# freeDSP.net
KiCad netlist of a schematic drawn in EAGLE
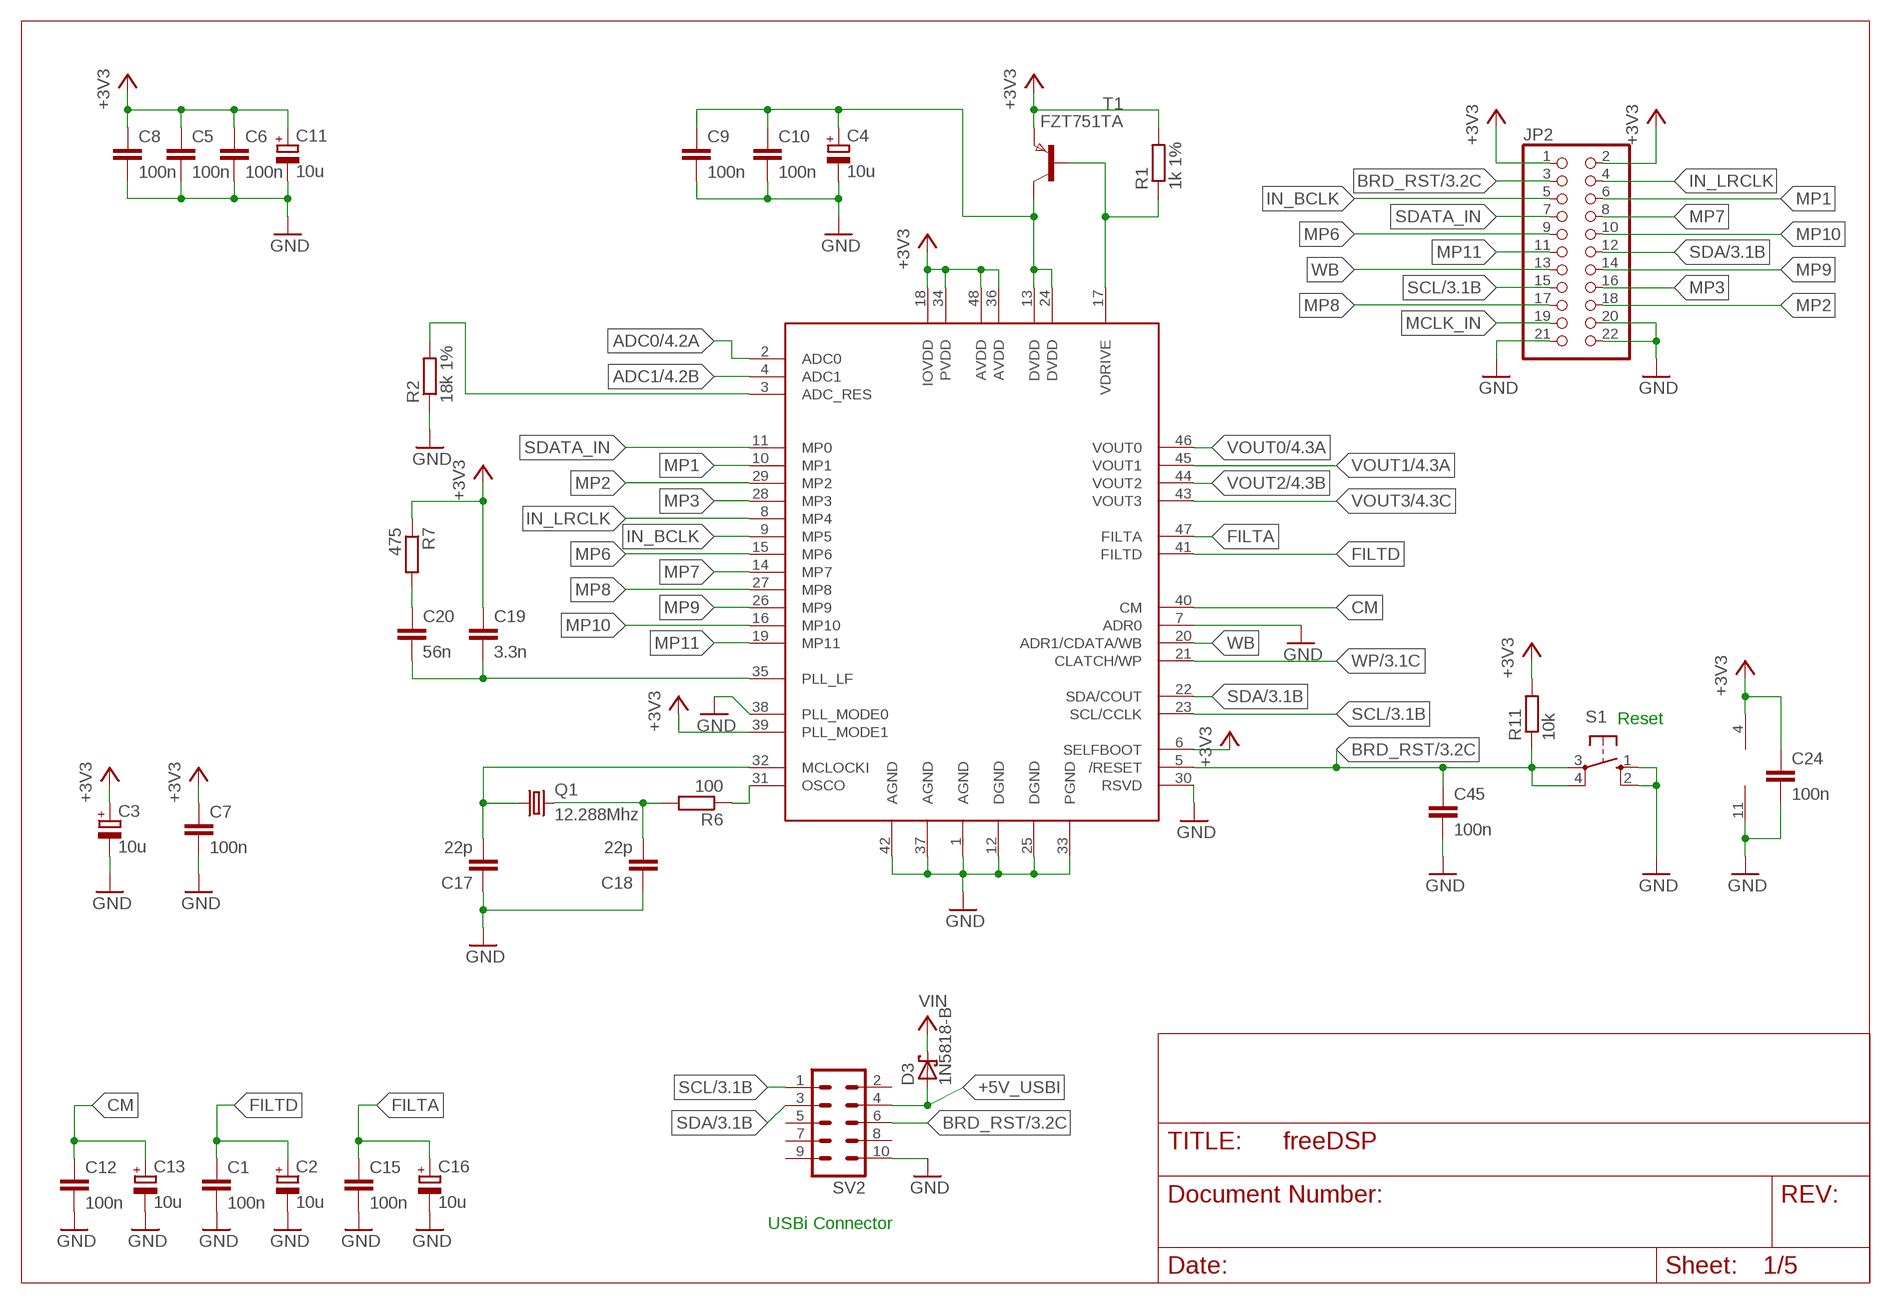
[diagram p0: schematic, sheet 1]
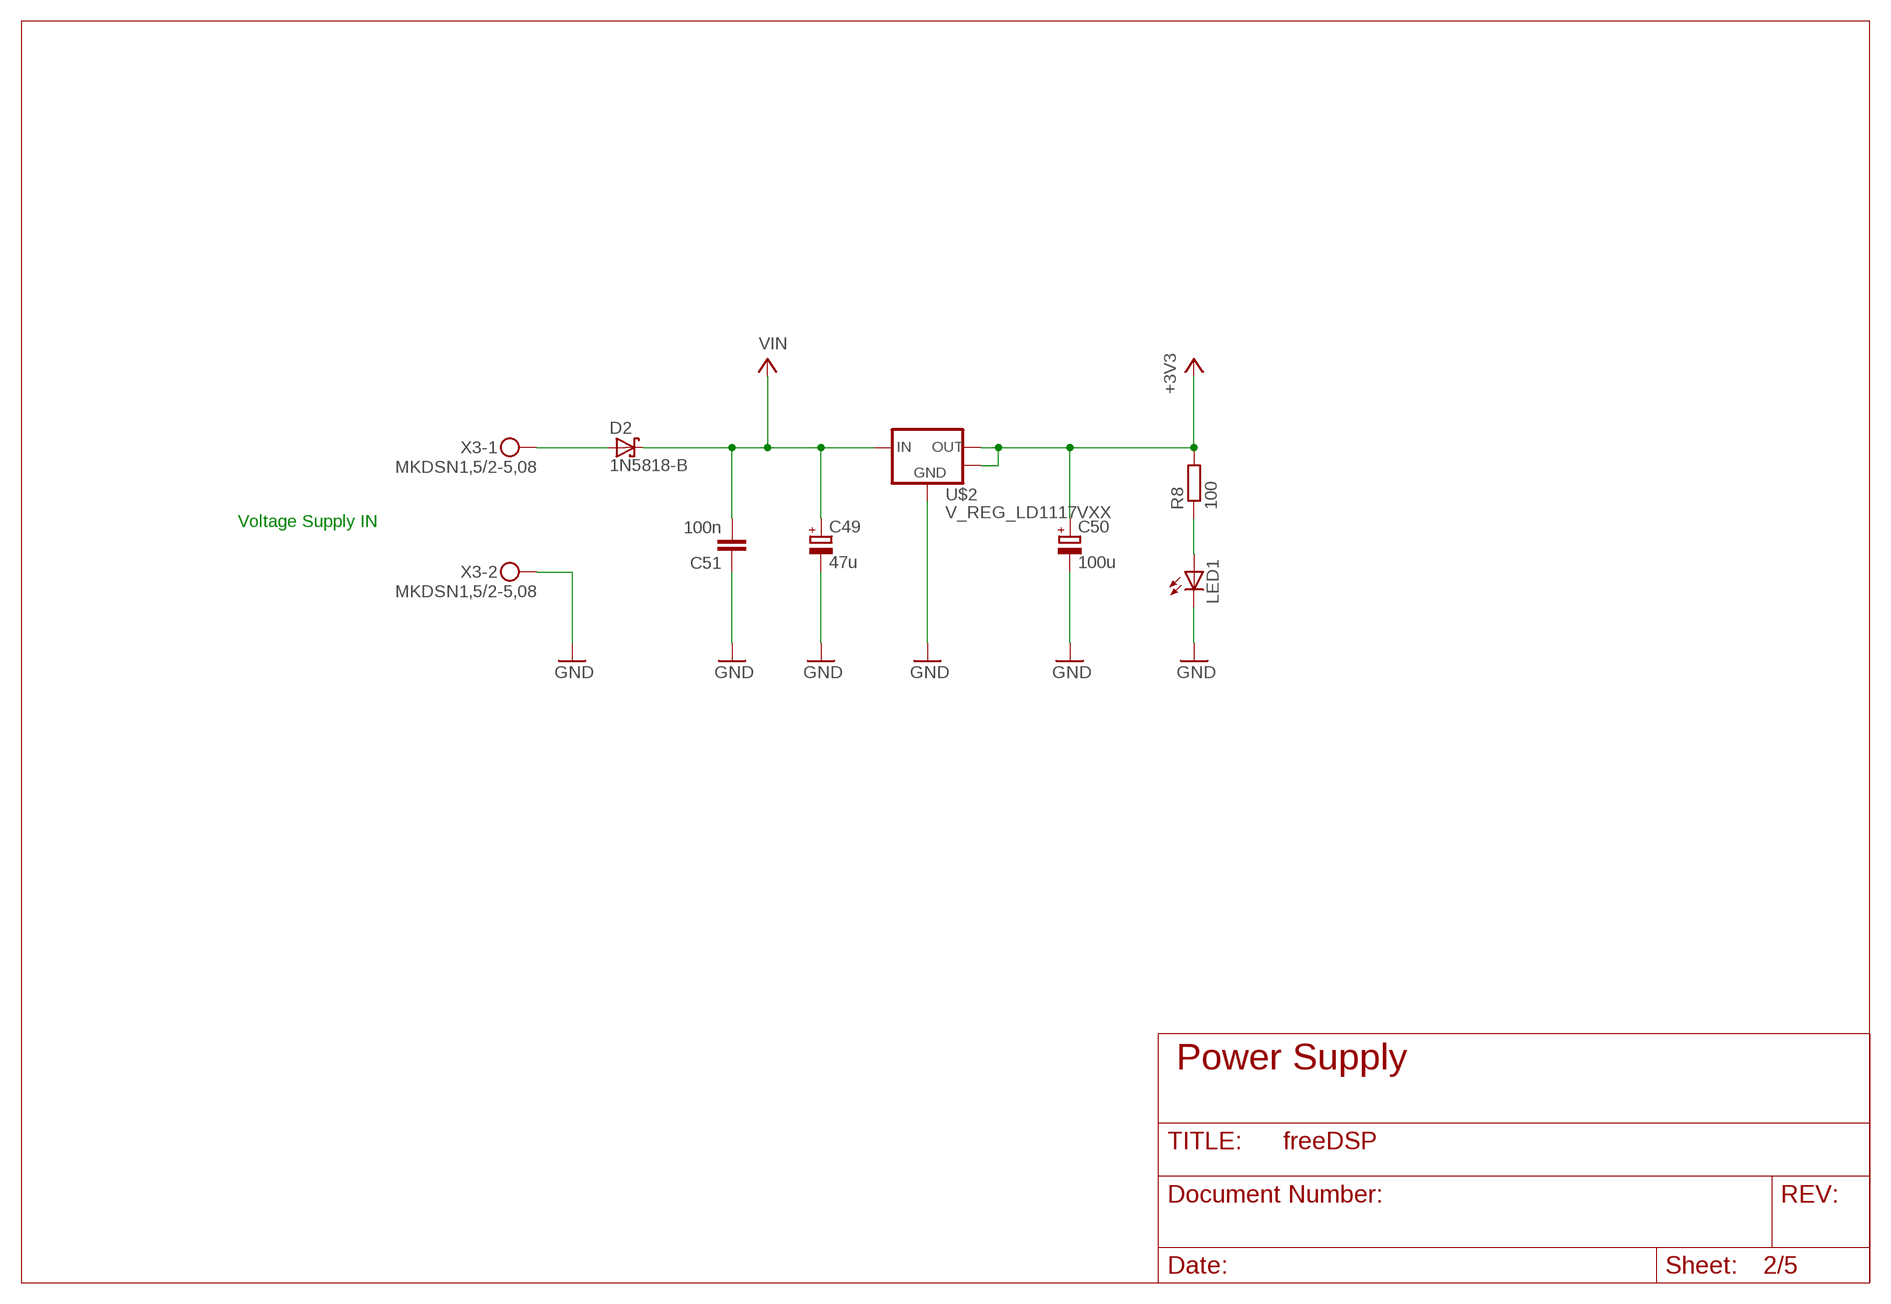
[diagram p1: schematic, sheet 2]
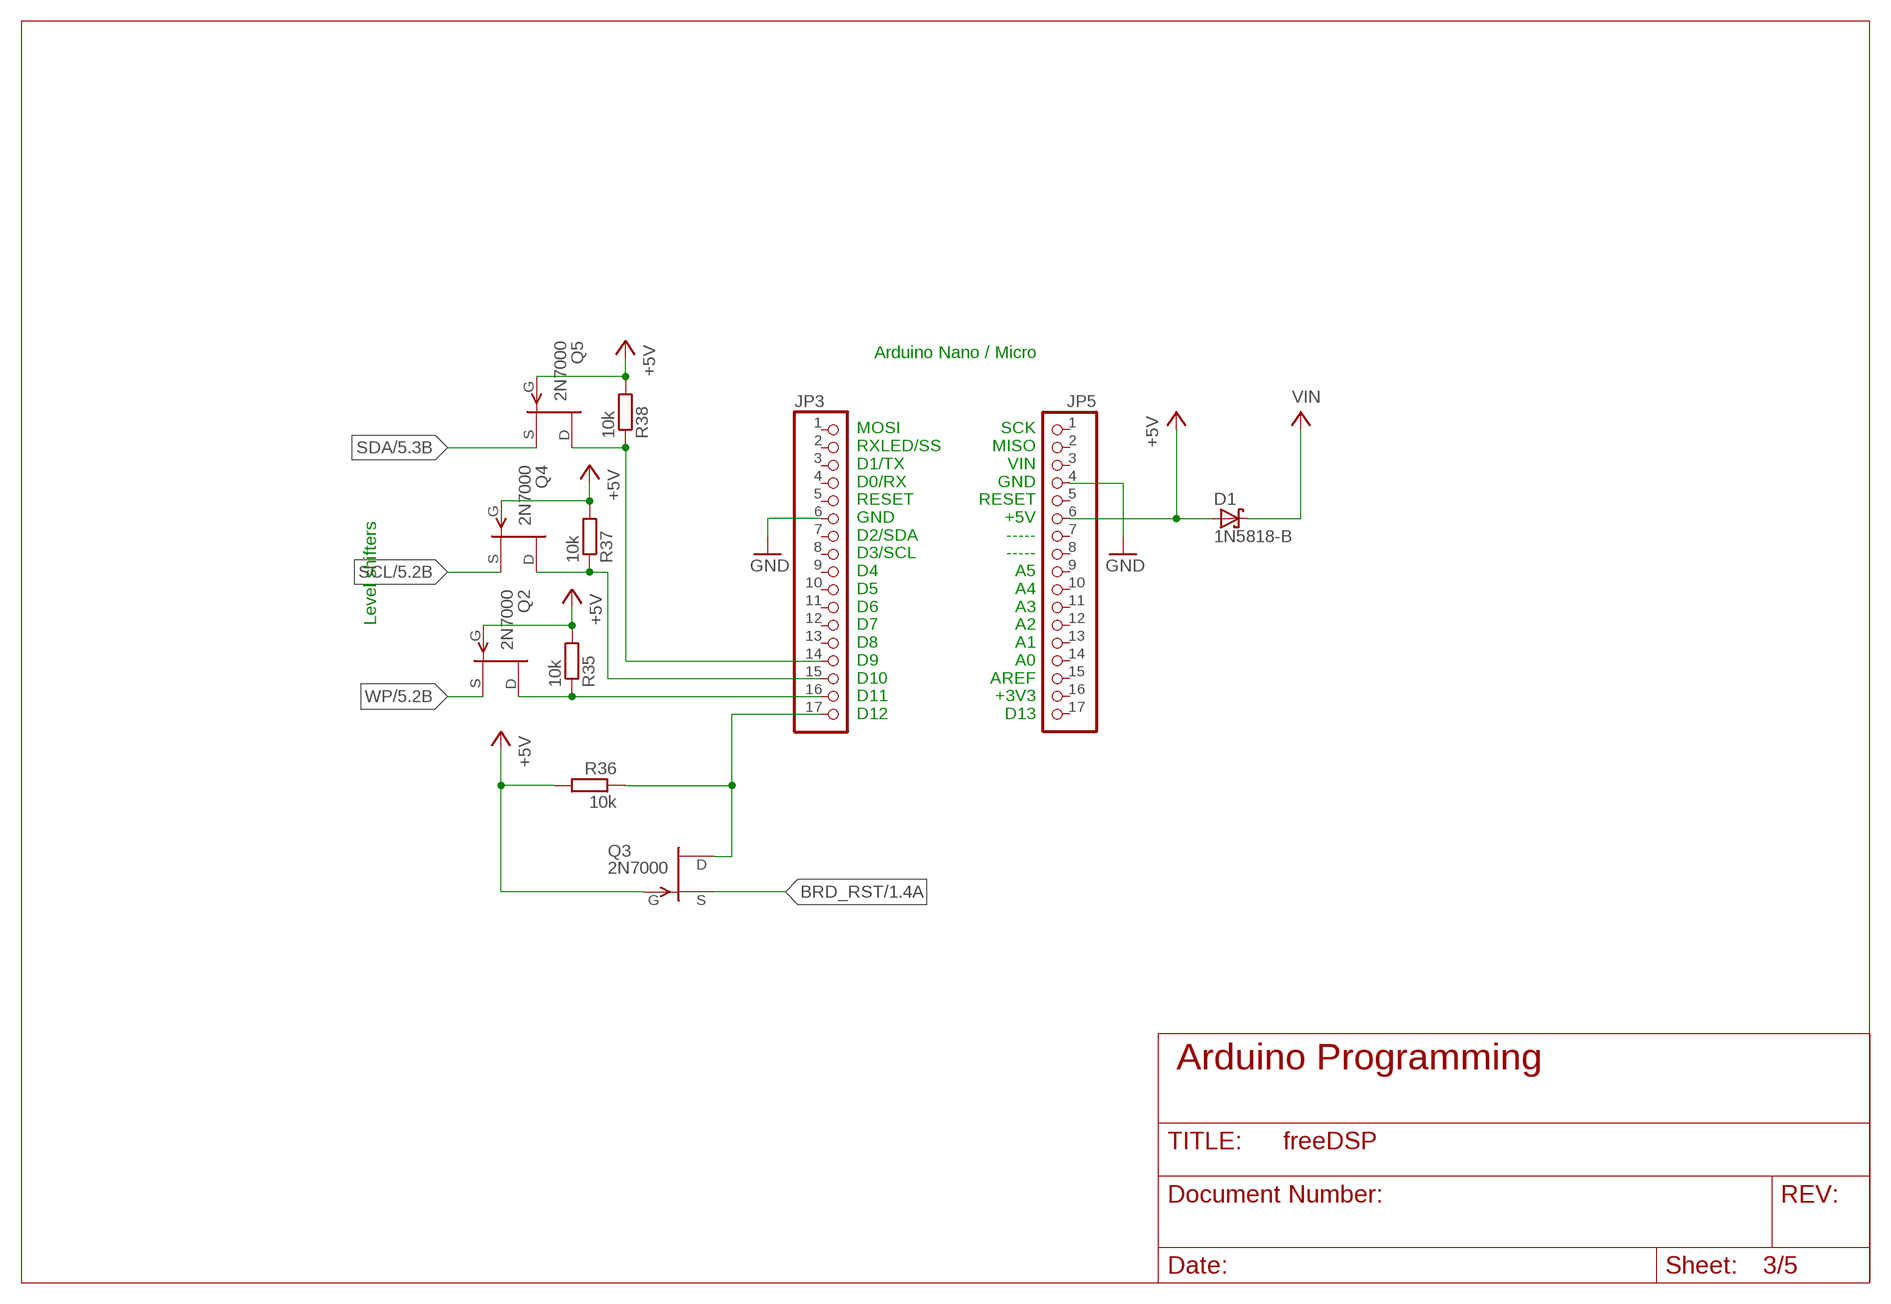
[diagram p2: schematic, sheet 3]
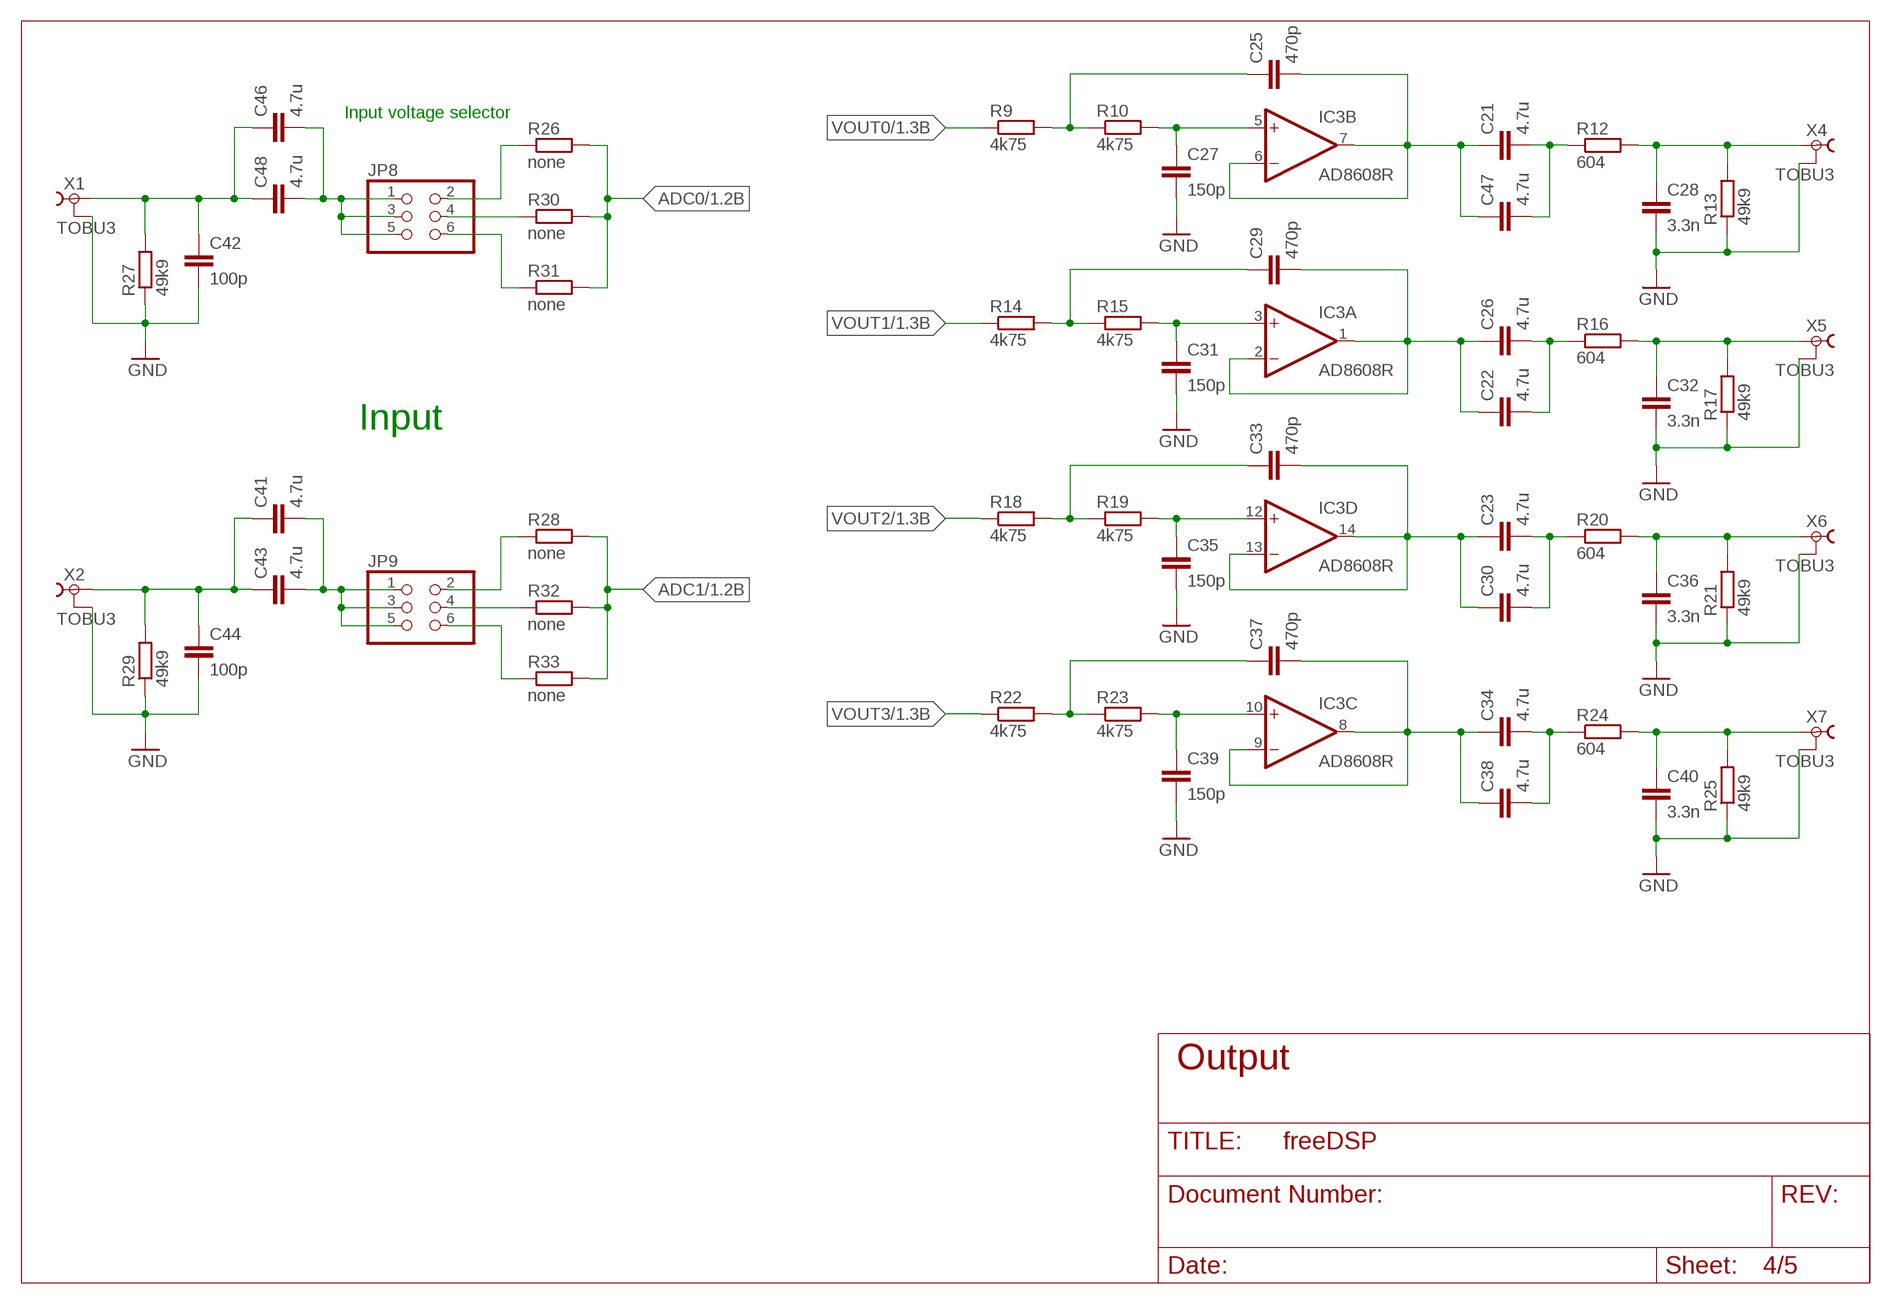
[diagram p3: schematic, sheet 4]
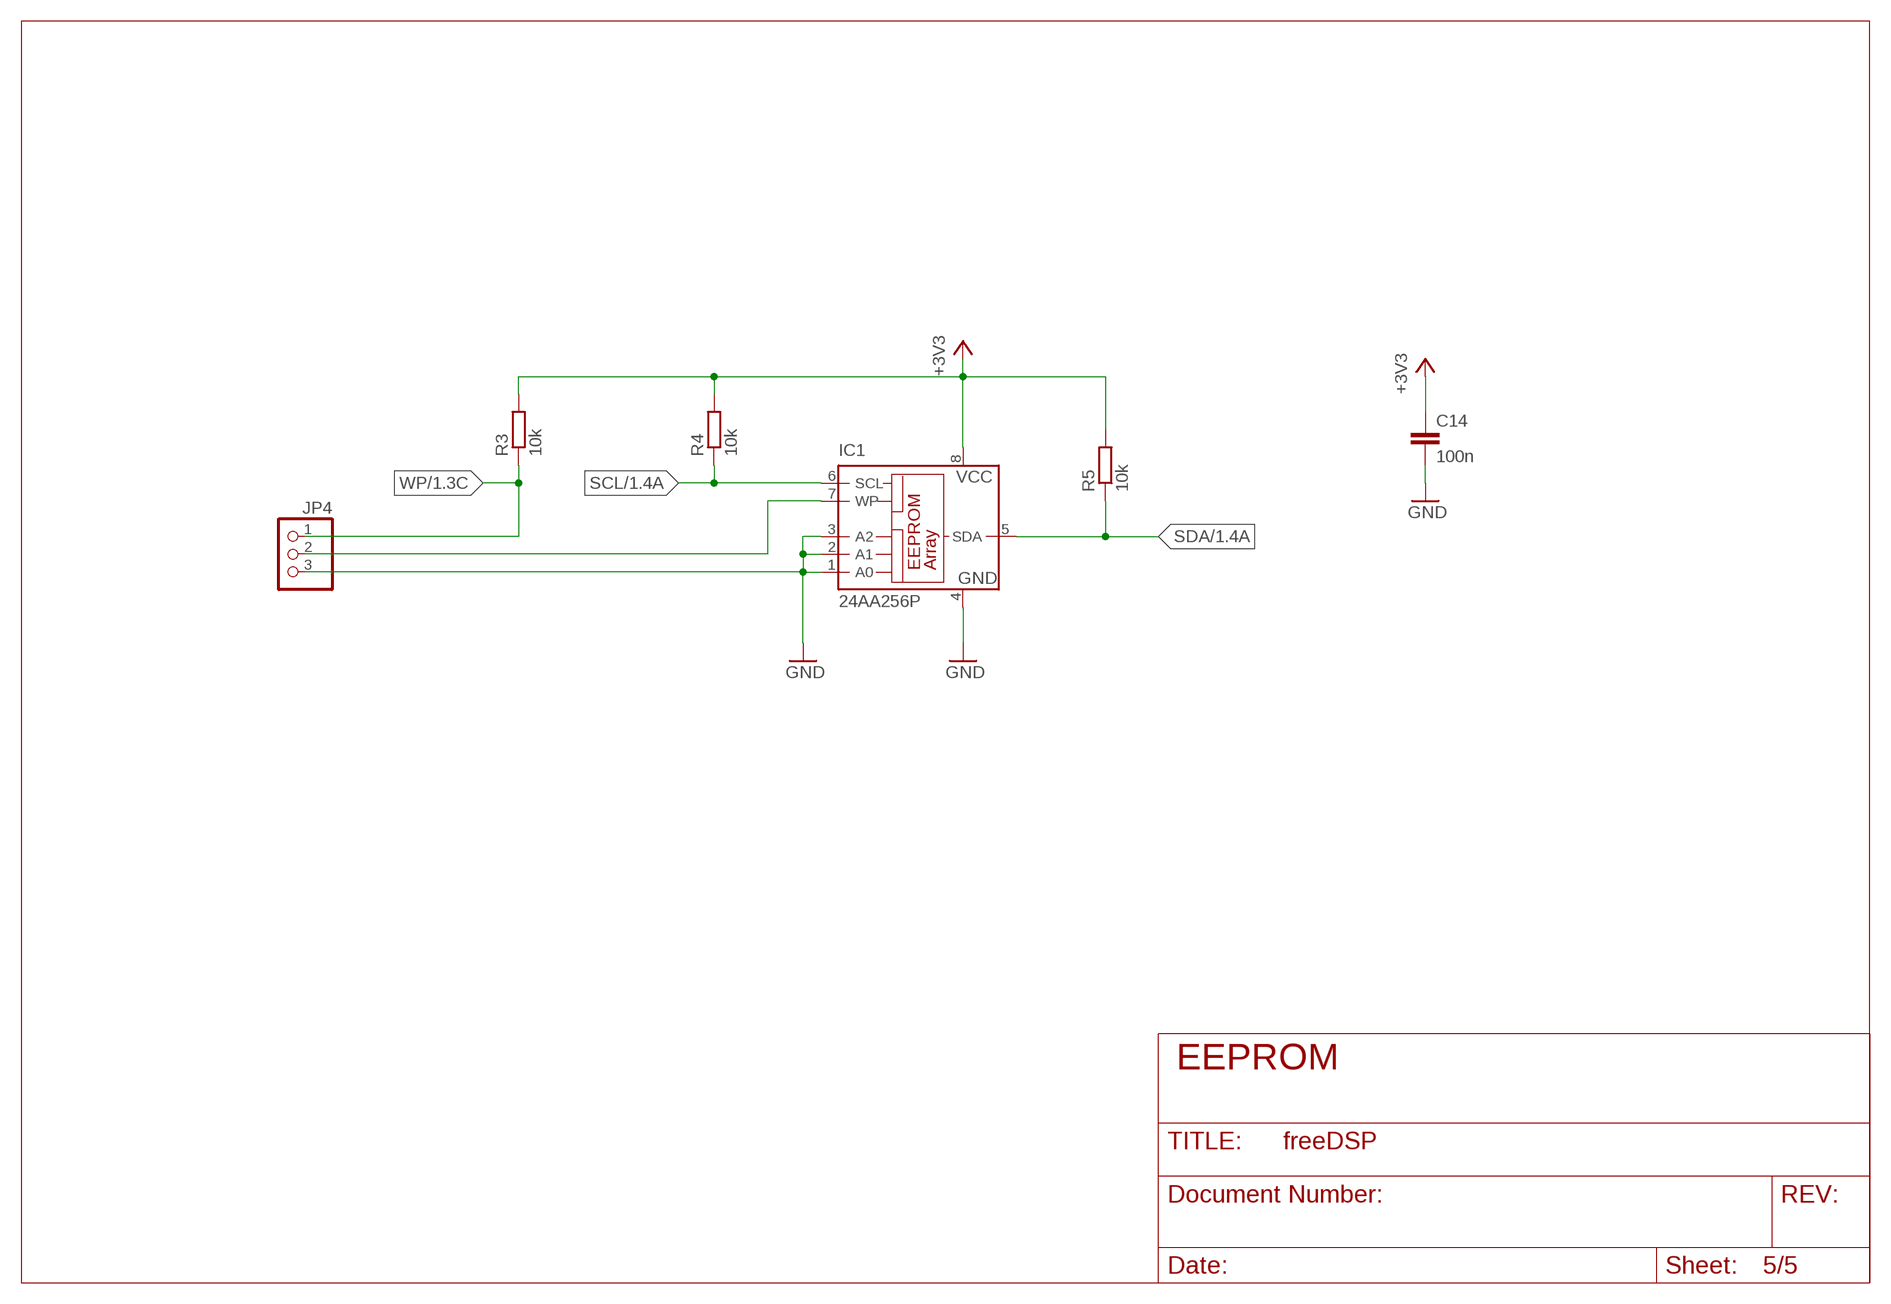
[diagram p4: schematic, sheet 5]

(export (version "E")
  (design (tool "Eeschema 10.0.6"))
  (components
    (comp (ref "C1")
      (value "100n")
      (footprint "eagle-import:C025-025X050")
      (libsource (lib "eagle-import") (part "C-EU025-025X050"))
    )
    (comp (ref "C2")
      (value "10u")
      (footprint "eagle-import:E1,8-4")
      (libsource (lib "eagle-import") (part "CPOL-EUE1.8-4"))
    )
    (comp (ref "C3")
      (value "10u")
      (footprint "eagle-import:E1,8-4")
      (libsource (lib "eagle-import") (part "CPOL-EUE1.8-4"))
    )
    (comp (ref "C4")
      (value "10u")
      (footprint "eagle-import:E1,8-4")
      (libsource (lib "eagle-import") (part "CPOL-EUE1.8-4"))
    )
    (comp (ref "C5")
      (value "100n")
      (footprint "eagle-import:C025-025X050")
      (libsource (lib "eagle-import") (part "C-EU025-025X050"))
    )
    (comp (ref "C6")
      (value "100n")
      (footprint "eagle-import:C025-025X050")
      (libsource (lib "eagle-import") (part "C-EU025-025X050"))
    )
    (comp (ref "C7")
      (value "100n")
      (footprint "eagle-import:C025-025X050")
      (libsource (lib "eagle-import") (part "C-EU025-025X050"))
    )
    (comp (ref "C8")
      (value "100n")
      (footprint "eagle-import:C025-025X050")
      (libsource (lib "eagle-import") (part "C-EU025-025X050"))
    )
    (comp (ref "C9")
      (value "100n")
      (footprint "eagle-import:C025-025X050")
      (libsource (lib "eagle-import") (part "C-EU025-025X050"))
    )
    (comp (ref "C10")
      (value "100n")
      (footprint "eagle-import:C025-025X050")
      (libsource (lib "eagle-import") (part "C-EU025-025X050"))
    )
    (comp (ref "C11")
      (value "10u")
      (footprint "eagle-import:E1,8-4")
      (libsource (lib "eagle-import") (part "CPOL-EUE1.8-4"))
    )
    (comp (ref "C12")
      (value "100n")
      (footprint "eagle-import:C025-025X050")
      (libsource (lib "eagle-import") (part "C-EU025-025X050"))
    )
    (comp (ref "C13")
      (value "10u")
      (footprint "eagle-import:E1,8-4")
      (libsource (lib "eagle-import") (part "CPOL-EUE1.8-4"))
    )
    (comp (ref "C15")
      (value "100n")
      (footprint "eagle-import:C025-025X050")
      (libsource (lib "eagle-import") (part "C-EU025-025X050"))
    )
    (comp (ref "C16")
      (value "10u")
      (footprint "eagle-import:E1,8-4")
      (libsource (lib "eagle-import") (part "CPOL-EUE1.8-4"))
    )
    (comp (ref "C17")
      (value "22p")
      (footprint "eagle-import:C025-025X050")
      (libsource (lib "eagle-import") (part "C-EU025-025X050"))
    )
    (comp (ref "C18")
      (value "22p")
      (footprint "eagle-import:C025-025X050")
      (libsource (lib "eagle-import") (part "C-EU025-025X050"))
    )
    (comp (ref "C19")
      (value "3.3n")
      (footprint "eagle-import:C025-025X050")
      (libsource (lib "eagle-import") (part "C-EU025-025X050"))
    )
    (comp (ref "C20")
      (value "56n")
      (footprint "eagle-import:C025-025X050")
      (libsource (lib "eagle-import") (part "C-EU025-025X050"))
    )
    (comp (ref "C24")
      (value "100n")
      (footprint "eagle-import:C025-025X050")
      (libsource (lib "eagle-import") (part "C-EU025-025X050"))
    )
    (comp (ref "C45")
      (value "100n")
      (footprint "eagle-import:C025-025X050")
      (libsource (lib "eagle-import") (part "C-EU025-025X050"))
    )
    (comp (ref "D3")
      (value "1N5818-B")
      (footprint "eagle-import:DO41-7.6")
      (libsource (lib "eagle-import") (part "1N5818-B"))
    )
    (comp (ref "IC3")
      (value "AD8608R")
      (footprint "eagle-import:SO-14")
      (libsource (lib "eagle-import") (part "AD8608R"))
    )
    (comp (ref "JP2")
      (value "PINHD-2X11")
      (footprint "eagle-import:2X11")
      (libsource (lib "eagle-import") (part "PINHD-2X11"))
    )
    (comp (ref "Q1")
      (value "12.288Mhz")
      (footprint "eagle-import:HC49_S")
      (libsource (lib "eagle-import") (part "CRYSTALHC49S"))
    )
    (comp (ref "R1")
      (value "1k 1%")
      (footprint "eagle-import:0207_10")
      (libsource (lib "eagle-import") (part "R-EU_0207/10"))
    )
    (comp (ref "R2")
      (value "18k 1%")
      (footprint "eagle-import:0207_10")
      (libsource (lib "eagle-import") (part "R-EU_0207/10"))
    )
    (comp (ref "R6")
      (value "100")
      (footprint "eagle-import:0207_10")
      (libsource (lib "eagle-import") (part "R-EU_0207/10"))
    )
    (comp (ref "R7")
      (value "475")
      (footprint "eagle-import:0207_10")
      (libsource (lib "eagle-import") (part "R-EU_0207/10"))
    )
    (comp (ref "R11")
      (value "10k")
      (footprint "eagle-import:0207_10")
      (libsource (lib "eagle-import") (part "R-EU_0207/10"))
    )
    (comp (ref "S1")
      (value "10-XX")
      (footprint "eagle-import:B3F-10XX")
      (fields (field (name "MPN") "B3F-1000"))
      (libsource (lib "eagle-import") (part "10-XX"))
    )
    (comp (ref "SV2")
      (value "ML10")
      (footprint "eagle-import:ML10")
      (libsource (lib "eagle-import") (part "ML10"))
    )
    (comp (ref "T1")
      (value "FZT751TA")
      (footprint "eagle-import:SOT223")
      (fields (field (name "MPN") "FZT789A"))
      (libsource (lib "eagle-import") (part "FZT789A"))
    )
    (comp (ref "U$1")
      (value "ADAU1701")
      (footprint "eagle-import:LQFP-48")
      (libsource (lib "eagle-import") (part "ADAU1701"))
    )
    (comp (ref "C14")
      (value "100n")
      (footprint "eagle-import:C025-025X050")
      (libsource (lib "eagle-import") (part "C-EU025-025X050"))
    )
    (comp (ref "IC1")
      (value "24AA256P")
      (footprint "eagle-import:DIL8")
      (fields (field (name "MF") "MICROCHIP") (field (name "MPN") "24AA256-I/P"))
      (libsource (lib "eagle-import") (part "24PAA256"))
    )
    (comp (ref "JP4")
      (value "PINHD-1X3")
      (footprint "eagle-import:1X03")
      (libsource (lib "eagle-import") (part "PINHD-1X3"))
    )
    (comp (ref "R3")
      (value "10k")
      (footprint "eagle-import:0207_10")
      (libsource (lib "eagle-import") (part "R-EU_0207/10"))
    )
    (comp (ref "R4")
      (value "10k")
      (footprint "eagle-import:0207_10")
      (libsource (lib "eagle-import") (part "R-EU_0207/10"))
    )
    (comp (ref "R5")
      (value "10k")
      (footprint "eagle-import:0207_10")
      (libsource (lib "eagle-import") (part "R-EU_0207/10"))
    )
    (comp (ref "D1")
      (value "1N5818-B")
      (footprint "eagle-import:DO41-7.6")
      (libsource (lib "eagle-import") (part "1N5818-B"))
    )
    (comp (ref "JP3")
      (value "PINHD-1X17")
      (footprint "eagle-import:1X17")
      (libsource (lib "eagle-import") (part "PINHD-1X17"))
    )
    (comp (ref "JP5")
      (value "PINHD-1X17")
      (footprint "eagle-import:1X17")
      (libsource (lib "eagle-import") (part "PINHD-1X17"))
    )
    (comp (ref "Q2")
      (value "2N7000")
      (footprint "eagle-import:TO92")
      (libsource (lib "eagle-import") (part "2N3819"))
    )
    (comp (ref "Q3")
      (value "2N7000")
      (footprint "eagle-import:TO92")
      (libsource (lib "eagle-import") (part "2N3819"))
    )
    (comp (ref "Q4")
      (value "2N7000")
      (footprint "eagle-import:TO92")
      (libsource (lib "eagle-import") (part "2N3819"))
    )
    (comp (ref "Q5")
      (value "2N7000")
      (footprint "eagle-import:TO92")
      (libsource (lib "eagle-import") (part "2N3819"))
    )
    (comp (ref "R35")
      (value "10k")
      (footprint "eagle-import:0207_10")
      (libsource (lib "eagle-import") (part "R-EU_0207/10"))
    )
    (comp (ref "R36")
      (value "10k")
      (footprint "eagle-import:0207_10")
      (libsource (lib "eagle-import") (part "R-EU_0207/10"))
    )
    (comp (ref "R37")
      (value "10k")
      (footprint "eagle-import:0207_10")
      (libsource (lib "eagle-import") (part "R-EU_0207/10"))
    )
    (comp (ref "R38")
      (value "10k")
      (footprint "eagle-import:0207_10")
      (libsource (lib "eagle-import") (part "R-EU_0207/10"))
    )
    (comp (ref "C21")
      (value "4.7u")
      (footprint "eagle-import:C050-075X075")
      (libsource (lib "eagle-import") (part "C-EU050-075X075"))
    )
    (comp (ref "C22")
      (value "4.7u")
      (footprint "eagle-import:C050-075X075")
      (libsource (lib "eagle-import") (part "C-EU050-075X075"))
    )
    (comp (ref "C23")
      (value "4.7u")
      (footprint "eagle-import:C050-075X075")
      (libsource (lib "eagle-import") (part "C-EU050-075X075"))
    )
    (comp (ref "C25")
      (value "470p")
      (footprint "eagle-import:C050-050X075")
      (libsource (lib "eagle-import") (part "C-EU050-050X075"))
    )
    (comp (ref "C26")
      (value "4.7u")
      (footprint "eagle-import:C050-075X075")
      (libsource (lib "eagle-import") (part "C-EU050-075X075"))
    )
    (comp (ref "C27")
      (value "150p")
      (footprint "eagle-import:C025-025X050")
      (libsource (lib "eagle-import") (part "C-EU025-025X050"))
    )
    (comp (ref "C28")
      (value "3.3n")
      (footprint "eagle-import:C025-025X050")
      (libsource (lib "eagle-import") (part "C-EU025-025X050"))
    )
    (comp (ref "C29")
      (value "470p")
      (footprint "eagle-import:C050-050X075")
      (libsource (lib "eagle-import") (part "C-EU050-050X075"))
    )
    (comp (ref "C30")
      (value "4.7u")
      (footprint "eagle-import:C050-075X075")
      (libsource (lib "eagle-import") (part "C-EU050-075X075"))
    )
    (comp (ref "C31")
      (value "150p")
      (footprint "eagle-import:C025-025X050")
      (libsource (lib "eagle-import") (part "C-EU025-025X050"))
    )
    (comp (ref "C32")
      (value "3.3n")
      (footprint "eagle-import:C025-025X050")
      (libsource (lib "eagle-import") (part "C-EU025-025X050"))
    )
    (comp (ref "C33")
      (value "470p")
      (footprint "eagle-import:C050-050X075")
      (libsource (lib "eagle-import") (part "C-EU050-050X075"))
    )
    (comp (ref "C34")
      (value "4.7u")
      (footprint "eagle-import:C050-075X075")
      (libsource (lib "eagle-import") (part "C-EU050-075X075"))
    )
    (comp (ref "C35")
      (value "150p")
      (footprint "eagle-import:C025-025X050")
      (libsource (lib "eagle-import") (part "C-EU025-025X050"))
    )
    (comp (ref "C36")
      (value "3.3n")
      (footprint "eagle-import:C025-025X050")
      (libsource (lib "eagle-import") (part "C-EU025-025X050"))
    )
    (comp (ref "C37")
      (value "470p")
      (footprint "eagle-import:C050-050X075")
      (libsource (lib "eagle-import") (part "C-EU050-050X075"))
    )
    (comp (ref "C38")
      (value "4.7u")
      (footprint "eagle-import:C050-075X075")
      (libsource (lib "eagle-import") (part "C-EU050-075X075"))
    )
    (comp (ref "C39")
      (value "150p")
      (footprint "eagle-import:C025-025X050")
      (libsource (lib "eagle-import") (part "C-EU025-025X050"))
    )
    (comp (ref "C40")
      (value "3.3n")
      (footprint "eagle-import:C025-025X050")
      (libsource (lib "eagle-import") (part "C-EU025-025X050"))
    )
    (comp (ref "C41")
      (value "4.7u")
      (footprint "eagle-import:C050-075X075")
      (libsource (lib "eagle-import") (part "C-EU050-075X075"))
    )
    (comp (ref "C42")
      (value "100p")
      (footprint "eagle-import:C025-025X050")
      (libsource (lib "eagle-import") (part "C-EU025-025X050"))
    )
    (comp (ref "C43")
      (value "4.7u")
      (footprint "eagle-import:C050-075X075")
      (libsource (lib "eagle-import") (part "C-EU050-075X075"))
    )
    (comp (ref "C44")
      (value "100p")
      (footprint "eagle-import:C025-025X050")
      (libsource (lib "eagle-import") (part "C-EU025-025X050"))
    )
    (comp (ref "C46")
      (value "4.7u")
      (footprint "eagle-import:C050-075X075")
      (libsource (lib "eagle-import") (part "C-EU050-075X075"))
    )
    (comp (ref "C47")
      (value "4.7u")
      (footprint "eagle-import:C050-075X075")
      (libsource (lib "eagle-import") (part "C-EU050-075X075"))
    )
    (comp (ref "C48")
      (value "4.7u")
      (footprint "eagle-import:C050-075X075")
      (libsource (lib "eagle-import") (part "C-EU050-075X075"))
    )
    (comp (ref "JP8")
      (value "PINHD-2X3")
      (footprint "eagle-import:2X03")
      (libsource (lib "eagle-import") (part "PINHD-2X3"))
    )
    (comp (ref "JP9")
      (value "PINHD-2X3")
      (footprint "eagle-import:2X03")
      (libsource (lib "eagle-import") (part "PINHD-2X3"))
    )
    (comp (ref "R9")
      (value "4k75")
      (footprint "eagle-import:0207_10")
      (libsource (lib "eagle-import") (part "R-EU_0207/10"))
    )
    (comp (ref "R10")
      (value "4k75")
      (footprint "eagle-import:0207_10")
      (libsource (lib "eagle-import") (part "R-EU_0207/10"))
    )
    (comp (ref "R12")
      (value "604")
      (footprint "eagle-import:0207_10")
      (libsource (lib "eagle-import") (part "R-EU_0207/10"))
    )
    (comp (ref "R13")
      (value "49k9")
      (footprint "eagle-import:0207_10")
      (libsource (lib "eagle-import") (part "R-EU_0207/10"))
    )
    (comp (ref "R14")
      (value "4k75")
      (footprint "eagle-import:0207_10")
      (libsource (lib "eagle-import") (part "R-EU_0207/10"))
    )
    (comp (ref "R15")
      (value "4k75")
      (footprint "eagle-import:0207_10")
      (libsource (lib "eagle-import") (part "R-EU_0207/10"))
    )
    (comp (ref "R16")
      (value "604")
      (footprint "eagle-import:0207_10")
      (libsource (lib "eagle-import") (part "R-EU_0207/10"))
    )
    (comp (ref "R17")
      (value "49k9")
      (footprint "eagle-import:0207_10")
      (libsource (lib "eagle-import") (part "R-EU_0207/10"))
    )
    (comp (ref "R18")
      (value "4k75")
      (footprint "eagle-import:0207_10")
      (libsource (lib "eagle-import") (part "R-EU_0207/10"))
    )
    (comp (ref "R19")
      (value "4k75")
      (footprint "eagle-import:0207_10")
      (libsource (lib "eagle-import") (part "R-EU_0207/10"))
    )
    (comp (ref "R20")
      (value "604")
      (footprint "eagle-import:0207_10")
      (libsource (lib "eagle-import") (part "R-EU_0207/10"))
    )
    (comp (ref "R21")
      (value "49k9")
      (footprint "eagle-import:0207_10")
      (libsource (lib "eagle-import") (part "R-EU_0207/10"))
    )
    (comp (ref "R22")
      (value "4k75")
      (footprint "eagle-import:0207_10")
      (libsource (lib "eagle-import") (part "R-EU_0207/10"))
    )
    (comp (ref "R23")
      (value "4k75")
      (footprint "eagle-import:0207_10")
      (libsource (lib "eagle-import") (part "R-EU_0207/10"))
    )
    (comp (ref "R24")
      (value "604")
      (footprint "eagle-import:0207_10")
      (libsource (lib "eagle-import") (part "R-EU_0207/10"))
    )
    (comp (ref "R25")
      (value "49k9")
      (footprint "eagle-import:0207_10")
      (libsource (lib "eagle-import") (part "R-EU_0207/10"))
    )
    (comp (ref "R26")
      (value "none")
      (footprint "eagle-import:0207_10")
      (libsource (lib "eagle-import") (part "R-EU_0207/10"))
    )
    (comp (ref "R27")
      (value "49k9")
      (footprint "eagle-import:0207_10")
      (libsource (lib "eagle-import") (part "R-EU_0207/10"))
    )
    (comp (ref "R28")
      (value "none")
      (footprint "eagle-import:0207_10")
      (libsource (lib "eagle-import") (part "R-EU_0207/10"))
    )
    (comp (ref "R29")
      (value "49k9")
      (footprint "eagle-import:0207_10")
      (libsource (lib "eagle-import") (part "R-EU_0207/10"))
    )
    (comp (ref "R30")
      (value "none")
      (footprint "eagle-import:0207_10")
      (libsource (lib "eagle-import") (part "R-EU_0207/10"))
    )
    (comp (ref "R31")
      (value "none")
      (footprint "eagle-import:0207_10")
      (libsource (lib "eagle-import") (part "R-EU_0207/10"))
    )
    (comp (ref "R32")
      (value "none")
      (footprint "eagle-import:0207_10")
      (libsource (lib "eagle-import") (part "R-EU_0207/10"))
    )
    (comp (ref "R33")
      (value "none")
      (footprint "eagle-import:0207_10")
      (libsource (lib "eagle-import") (part "R-EU_0207/10"))
    )
    (comp (ref "X1")
      (value "TOBU3")
      (footprint "eagle-import:TOBU3")
      (fields (field (name "MF") "FARNELL") (field (name "MPN") "TOBU 3"))
      (libsource (lib "eagle-import") (part "TOBU3"))
    )
    (comp (ref "X2")
      (value "TOBU3")
      (footprint "eagle-import:TOBU3")
      (fields (field (name "MF") "FARNELL") (field (name "MPN") "TOBU 3"))
      (libsource (lib "eagle-import") (part "TOBU3"))
    )
    (comp (ref "X4")
      (value "TOBU3")
      (footprint "eagle-import:TOBU3")
      (fields (field (name "MF") "FARNELL") (field (name "MPN") "TOBU 3"))
      (libsource (lib "eagle-import") (part "TOBU3"))
    )
    (comp (ref "X5")
      (value "TOBU3")
      (footprint "eagle-import:TOBU3")
      (fields (field (name "MF") "FARNELL") (field (name "MPN") "TOBU 3"))
      (libsource (lib "eagle-import") (part "TOBU3"))
    )
    (comp (ref "X6")
      (value "TOBU3")
      (footprint "eagle-import:TOBU3")
      (fields (field (name "MF") "FARNELL") (field (name "MPN") "TOBU 3"))
      (libsource (lib "eagle-import") (part "TOBU3"))
    )
    (comp (ref "X7")
      (value "TOBU3")
      (footprint "eagle-import:TOBU3")
      (fields (field (name "MF") "FARNELL") (field (name "MPN") "TOBU 3"))
      (libsource (lib "eagle-import") (part "TOBU3"))
    )
    (comp (ref "C49")
      (value "47u")
      (footprint "eagle-import:E2,5-6")
      (libsource (lib "eagle-import") (part "CPOL-EUE2.5-6"))
    )
    (comp (ref "C50")
      (value "100u")
      (footprint "eagle-import:E2,5-6")
      (libsource (lib "eagle-import") (part "CPOL-EUE2.5-6"))
    )
    (comp (ref "C51")
      (value "100n")
      (footprint "eagle-import:C025-025X050")
      (libsource (lib "eagle-import") (part "C-EU025-025X050"))
    )
    (comp (ref "D2")
      (value "1N5818-B")
      (footprint "eagle-import:DO41-7.6")
      (libsource (lib "eagle-import") (part "1N5818-B"))
    )
    (comp (ref "LED1")
      (value "LED3MM")
      (footprint "eagle-import:LED3MM")
      (libsource (lib "eagle-import") (part "LED3MM"))
    )
    (comp (ref "R8")
      (value "100")
      (footprint "eagle-import:0207_10")
      (libsource (lib "eagle-import") (part "R-EU_0207/10"))
    )
    (comp (ref "U$2")
      (value "V_REG_LD1117VXX")
      (footprint "eagle-import:78XXL")
      (libsource (lib "eagle-import") (part "V_REG_LD1117VXX"))
    )
    (comp (ref "X3")
      (value "MKDSN1,5/2-5,08")
      (footprint "eagle-import:MKDSN1,5_2-5,08")
      (fields (field (name "MPN") "MKDSN 1,5/2-5.08"))
      (libsource (lib "eagle-import") (part "MKDSN1,5/2-5,08"))
    )
  )
  (nets
    (net (code "1") (name "+3V3") (class "Default")
      (node (ref "C11") (pin "+") (pinfunction "+_+") (pintype "passive"))
      (node (ref "C14") (pin "1") (pinfunction "1_1") (pintype "passive"))
      (node (ref "C19") (pin "1") (pinfunction "1_1") (pintype "passive"))
      (node (ref "C24") (pin "1") (pinfunction "1_1") (pintype "passive"))
      (node (ref "C3") (pin "+") (pinfunction "+_+") (pintype "passive"))
      (node (ref "C5") (pin "1") (pinfunction "1_1") (pintype "passive"))
      (node (ref "C50") (pin "+") (pinfunction "+_+") (pintype "passive"))
      (node (ref "C6") (pin "1") (pinfunction "1_1") (pintype "passive"))
      (node (ref "C7") (pin "1") (pinfunction "1_1") (pintype "passive"))
      (node (ref "C8") (pin "1") (pinfunction "1_1") (pintype "passive"))
      (node (ref "IC1") (pin "8") (pinfunction "VCC_8") (pintype "power_in"))
      (node (ref "IC3") (pin "4") (pinfunction "V+_4") (pintype "power_in"))
      (node (ref "JP2") (pin "1") (pinfunction "1_1") (pintype "passive"))
      (node (ref "JP2") (pin "2") (pinfunction "2_2") (pintype "passive"))
      (node (ref "R1") (pin "2") (pinfunction "2_2") (pintype "passive"))
      (node (ref "R11") (pin "2") (pinfunction "2_2") (pintype "passive"))
      (node (ref "R3") (pin "2") (pinfunction "2_2") (pintype "passive"))
      (node (ref "R4") (pin "2") (pinfunction "2_2") (pintype "passive"))
      (node (ref "R5") (pin "2") (pinfunction "2_2") (pintype "passive"))
      (node (ref "R7") (pin "1") (pinfunction "1_1") (pintype "passive"))
      (node (ref "R8") (pin "2") (pinfunction "2_2") (pintype "passive"))
      (node (ref "T1") (pin "3") (pinfunction "E_3") (pintype "passive"))
      (node (ref "U$1") (pin "18") (pinfunction "IOVDD_18") (pintype "power_in"))
      (node (ref "U$1") (pin "34") (pinfunction "PVDD_34") (pintype "power_in"))
      (node (ref "U$1") (pin "36") (pinfunction "AVDD_36") (pintype "power_in"))
      (node (ref "U$1") (pin "39") (pinfunction "PLL_MODE1_39") (pintype "bidirectional"))
      (node (ref "U$1") (pin "48") (pinfunction "AVDD_48") (pintype "power_in"))
      (node (ref "U$1") (pin "6") (pinfunction "SELFBOOT_6") (pintype "bidirectional"))
      (node (ref "U$2") (pin "GND") (pinfunction "OUT_GND") (pintype "output"))
      (node (ref "U$2") (pin "OUT2") (pinfunction "OUT2_OUT2") (pintype "output"))
    )
    (net (code "2") (name "+5V") (class "Default")
      (node (ref "D1") (pin "A") (pinfunction "A_A") (pintype "passive"))
      (node (ref "JP5") (pin "6") (pinfunction "6_6") (pintype "passive"))
      (node (ref "Q2") (pin "2") (pinfunction "G_2") (pintype "passive"))
      (node (ref "Q3") (pin "2") (pinfunction "G_2") (pintype "passive"))
      (node (ref "Q4") (pin "2") (pinfunction "G_2") (pintype "passive"))
      (node (ref "Q5") (pin "2") (pinfunction "G_2") (pintype "passive"))
      (node (ref "R35") (pin "2") (pinfunction "2_2") (pintype "passive"))
      (node (ref "R36") (pin "2") (pinfunction "2_2") (pintype "passive"))
      (node (ref "R37") (pin "2") (pinfunction "2_2") (pintype "passive"))
      (node (ref "R38") (pin "2") (pinfunction "2_2") (pintype "passive"))
    )
    (net (code "3") (name "+5V_USBI") (class "Default")
      (node (ref "D3") (pin "A") (pinfunction "A_A") (pintype "passive"))
      (node (ref "SV2") (pin "4") (pinfunction "4_4") (pintype "passive"))
    )
    (net (code "4") (name "ADC0") (class "Default")
      (node (ref "R26") (pin "2") (pinfunction "2_2") (pintype "passive"))
      (node (ref "R30") (pin "2") (pinfunction "2_2") (pintype "passive"))
      (node (ref "R31") (pin "2") (pinfunction "2_2") (pintype "passive"))
      (node (ref "U$1") (pin "2") (pinfunction "ADC0_2") (pintype "bidirectional"))
    )
    (net (code "5") (name "ADC1") (class "Default")
      (node (ref "R28") (pin "2") (pinfunction "2_2") (pintype "passive"))
      (node (ref "R32") (pin "2") (pinfunction "2_2") (pintype "passive"))
      (node (ref "R33") (pin "2") (pinfunction "2_2") (pintype "passive"))
      (node (ref "U$1") (pin "4") (pinfunction "ADC1_4") (pintype "bidirectional"))
    )
    (net (code "6") (name "BRD_RST") (class "Default")
      (node (ref "C45") (pin "1") (pinfunction "1_1") (pintype "passive"))
      (node (ref "JP2") (pin "3") (pinfunction "3_3") (pintype "passive"))
      (node (ref "Q3") (pin "3") (pinfunction "S_3") (pintype "passive"))
      (node (ref "R11") (pin "1") (pinfunction "1_1") (pintype "passive"))
      (node (ref "S1") (pin "3") (pinfunction "P_3") (pintype "passive"))
      (node (ref "S1") (pin "4") (pinfunction "P1_4") (pintype "passive"))
      (node (ref "SV2") (pin "6") (pinfunction "6_6") (pintype "passive"))
      (node (ref "U$1") (pin "5") (pinfunction "/RESET_5") (pintype "bidirectional"))
    )
    (net (code "7") (name "CM") (class "Default")
      (node (ref "C12") (pin "1") (pinfunction "1_1") (pintype "passive"))
      (node (ref "C13") (pin "+") (pinfunction "+_+") (pintype "passive"))
      (node (ref "U$1") (pin "40") (pinfunction "CM_40") (pintype "bidirectional"))
    )
    (net (code "8") (name "FILTA") (class "Default")
      (node (ref "C15") (pin "1") (pinfunction "1_1") (pintype "passive"))
      (node (ref "C16") (pin "+") (pinfunction "+_+") (pintype "passive"))
      (node (ref "U$1") (pin "47") (pinfunction "FILTA_47") (pintype "bidirectional"))
    )
    (net (code "9") (name "FILTD") (class "Default")
      (node (ref "C1") (pin "1") (pinfunction "1_1") (pintype "passive"))
      (node (ref "C2") (pin "+") (pinfunction "+_+") (pintype "passive"))
      (node (ref "U$1") (pin "41") (pinfunction "FILTD_41") (pintype "bidirectional"))
    )
    (net (code "10") (name "GND") (class "Default")
      (node (ref "C1") (pin "2") (pinfunction "2_2") (pintype "passive"))
      (node (ref "C10") (pin "2") (pinfunction "2_2") (pintype "passive"))
      (node (ref "C11") (pin "-") (pinfunction "-_-") (pintype "passive"))
      (node (ref "C12") (pin "2") (pinfunction "2_2") (pintype "passive"))
      (node (ref "C13") (pin "-") (pinfunction "-_-") (pintype "passive"))
      (node (ref "C14") (pin "2") (pinfunction "2_2") (pintype "passive"))
      (node (ref "C15") (pin "2") (pinfunction "2_2") (pintype "passive"))
      (node (ref "C16") (pin "-") (pinfunction "-_-") (pintype "passive"))
      (node (ref "C17") (pin "1") (pinfunction "1_1") (pintype "passive"))
      (node (ref "C18") (pin "1") (pinfunction "1_1") (pintype "passive"))
      (node (ref "C2") (pin "-") (pinfunction "-_-") (pintype "passive"))
      (node (ref "C24") (pin "2") (pinfunction "2_2") (pintype "passive"))
      (node (ref "C27") (pin "2") (pinfunction "2_2") (pintype "passive"))
      (node (ref "C28") (pin "2") (pinfunction "2_2") (pintype "passive"))
      (node (ref "C3") (pin "-") (pinfunction "-_-") (pintype "passive"))
      (node (ref "C31") (pin "2") (pinfunction "2_2") (pintype "passive"))
      (node (ref "C32") (pin "2") (pinfunction "2_2") (pintype "passive"))
      (node (ref "C35") (pin "2") (pinfunction "2_2") (pintype "passive"))
      (node (ref "C36") (pin "2") (pinfunction "2_2") (pintype "passive"))
      (node (ref "C39") (pin "2") (pinfunction "2_2") (pintype "passive"))
      (node (ref "C4") (pin "-") (pinfunction "-_-") (pintype "passive"))
      (node (ref "C40") (pin "2") (pinfunction "2_2") (pintype "passive"))
      (node (ref "C42") (pin "2") (pinfunction "2_2") (pintype "passive"))
      (node (ref "C44") (pin "2") (pinfunction "2_2") (pintype "passive"))
      (node (ref "C45") (pin "2") (pinfunction "2_2") (pintype "passive"))
      (node (ref "C49") (pin "-") (pinfunction "-_-") (pintype "passive"))
      (node (ref "C5") (pin "2") (pinfunction "2_2") (pintype "passive"))
      (node (ref "C50") (pin "-") (pinfunction "-_-") (pintype "passive"))
      (node (ref "C51") (pin "1") (pinfunction "1_1") (pintype "passive"))
      (node (ref "C6") (pin "2") (pinfunction "2_2") (pintype "passive"))
      (node (ref "C7") (pin "2") (pinfunction "2_2") (pintype "passive"))
      (node (ref "C8") (pin "2") (pinfunction "2_2") (pintype "passive"))
      (node (ref "C9") (pin "2") (pinfunction "2_2") (pintype "passive"))
      (node (ref "IC1") (pin "1") (pinfunction "A0_1") (pintype "input"))
      (node (ref "IC1") (pin "2") (pinfunction "A1_2") (pintype "input"))
      (node (ref "IC1") (pin "3") (pinfunction "A2_3") (pintype "input"))
      (node (ref "IC1") (pin "4") (pinfunction "GND_4") (pintype "power_in"))
      (node (ref "IC3") (pin "11") (pinfunction "V-_11") (pintype "power_in"))
      (node (ref "JP2") (pin "20") (pinfunction "20_20") (pintype "passive"))
      (node (ref "JP2") (pin "21") (pinfunction "21_21") (pintype "passive"))
      (node (ref "JP2") (pin "22") (pinfunction "22_22") (pintype "passive"))
      (node (ref "JP3") (pin "6") (pinfunction "6_6") (pintype "passive"))
      (node (ref "JP4") (pin "3") (pinfunction "3_3") (pintype "passive"))
      (node (ref "JP5") (pin "4") (pinfunction "4_4") (pintype "passive"))
      (node (ref "LED1") (pin "K") (pinfunction "C_K") (pintype "passive"))
      (node (ref "R13") (pin "1") (pinfunction "1_1") (pintype "passive"))
      (node (ref "R17") (pin "1") (pinfunction "1_1") (pintype "passive"))
      (node (ref "R2") (pin "1") (pinfunction "1_1") (pintype "passive"))
      (node (ref "R21") (pin "1") (pinfunction "1_1") (pintype "passive"))
      (node (ref "R25") (pin "1") (pinfunction "1_1") (pintype "passive"))
      (node (ref "R27") (pin "1") (pinfunction "1_1") (pintype "passive"))
      (node (ref "R29") (pin "1") (pinfunction "1_1") (pintype "passive"))
      (node (ref "S1") (pin "1") (pinfunction "S_1") (pintype "passive"))
      (node (ref "S1") (pin "2") (pinfunction "S1_2") (pintype "passive"))
      (node (ref "SV2") (pin "10") (pinfunction "10_10") (pintype "passive"))
      (node (ref "U$1") (pin "1") (pinfunction "AGND_1") (pintype "power_in"))
      (node (ref "U$1") (pin "12") (pinfunction "DGND_12") (pintype "power_in"))
      (node (ref "U$1") (pin "25") (pinfunction "DGND_25") (pintype "power_in"))
      (node (ref "U$1") (pin "30") (pinfunction "RSVD_30") (pintype "bidirectional"))
      (node (ref "U$1") (pin "33") (pinfunction "PGND_33") (pintype "power_in"))
      (node (ref "U$1") (pin "37") (pinfunction "AGND_37") (pintype "power_in"))
      (node (ref "U$1") (pin "38") (pinfunction "PLL_MODE0_38") (pintype "bidirectional"))
      (node (ref "U$1") (pin "42") (pinfunction "AGND_42") (pintype "power_in"))
      (node (ref "U$1") (pin "7") (pinfunction "ADR0_7") (pintype "bidirectional"))
      (node (ref "U$2") (pin "IN") (pinfunction "GND_IN") (pintype "input"))
      (node (ref "X1") (pin "2") (pinfunction "2_2") (pintype "passive"))
      (node (ref "X1") (pin "2@1") (pinfunction "2_2@1") (pintype "passive"))
      (node (ref "X1") (pin "2@2") (pinfunction "2_2@2") (pintype "passive"))
      (node (ref "X2") (pin "2") (pinfunction "2_2") (pintype "passive"))
      (node (ref "X2") (pin "2@1") (pinfunction "2_2@1") (pintype "passive"))
      (node (ref "X2") (pin "2@2") (pinfunction "2_2@2") (pintype "passive"))
      (node (ref "X3") (pin "2") (pinfunction "KL_2") (pintype "passive"))
      (node (ref "X4") (pin "2") (pinfunction "2_2") (pintype "passive"))
      (node (ref "X4") (pin "2@1") (pinfunction "2_2@1") (pintype "passive"))
      (node (ref "X4") (pin "2@2") (pinfunction "2_2@2") (pintype "passive"))
      (node (ref "X5") (pin "2") (pinfunction "2_2") (pintype "passive"))
      (node (ref "X5") (pin "2@1") (pinfunction "2_2@1") (pintype "passive"))
      (node (ref "X5") (pin "2@2") (pinfunction "2_2@2") (pintype "passive"))
      (node (ref "X6") (pin "2") (pinfunction "2_2") (pintype "passive"))
      (node (ref "X6") (pin "2@1") (pinfunction "2_2@1") (pintype "passive"))
      (node (ref "X6") (pin "2@2") (pinfunction "2_2@2") (pintype "passive"))
      (node (ref "X7") (pin "2") (pinfunction "2_2") (pintype "passive"))
      (node (ref "X7") (pin "2@1") (pinfunction "2_2@1") (pintype "passive"))
      (node (ref "X7") (pin "2@2") (pinfunction "2_2@2") (pintype "passive"))
    )
    (net (code "11") (name "IN_BCLK") (class "Default")
      (node (ref "JP2") (pin "5") (pinfunction "5_5") (pintype "passive"))
      (node (ref "U$1") (pin "9") (pinfunction "MP5_9") (pintype "bidirectional"))
    )
    (net (code "12") (name "IN_LRCLK") (class "Default")
      (node (ref "JP2") (pin "4") (pinfunction "4_4") (pintype "passive"))
      (node (ref "U$1") (pin "8") (pinfunction "MP4_8") (pintype "bidirectional"))
    )
    (net (code "13") (name "MCLK_IN") (class "Default")
      (node (ref "JP2") (pin "19") (pinfunction "19_19") (pintype "passive"))
    )
    (net (code "14") (name "MP1") (class "Default")
      (node (ref "JP2") (pin "6") (pinfunction "6_6") (pintype "passive"))
      (node (ref "U$1") (pin "10") (pinfunction "MP1_10") (pintype "bidirectional"))
    )
    (net (code "15") (name "MP2") (class "Default")
      (node (ref "JP2") (pin "18") (pinfunction "18_18") (pintype "passive"))
      (node (ref "U$1") (pin "29") (pinfunction "MP2_29") (pintype "bidirectional"))
    )
    (net (code "16") (name "MP3") (class "Default")
      (node (ref "JP2") (pin "16") (pinfunction "16_16") (pintype "passive"))
      (node (ref "U$1") (pin "28") (pinfunction "MP3_28") (pintype "bidirectional"))
    )
    (net (code "17") (name "MP6") (class "Default")
      (node (ref "JP2") (pin "9") (pinfunction "9_9") (pintype "passive"))
      (node (ref "U$1") (pin "15") (pinfunction "MP6_15") (pintype "bidirectional"))
    )
    (net (code "18") (name "MP7") (class "Default")
      (node (ref "JP2") (pin "8") (pinfunction "8_8") (pintype "passive"))
      (node (ref "U$1") (pin "14") (pinfunction "MP7_14") (pintype "bidirectional"))
    )
    (net (code "19") (name "MP8") (class "Default")
      (node (ref "JP2") (pin "17") (pinfunction "17_17") (pintype "passive"))
      (node (ref "U$1") (pin "27") (pinfunction "MP8_27") (pintype "bidirectional"))
    )
    (net (code "20") (name "MP9") (class "Default")
      (node (ref "JP2") (pin "14") (pinfunction "14_14") (pintype "passive"))
      (node (ref "U$1") (pin "26") (pinfunction "MP9_26") (pintype "bidirectional"))
    )
    (net (code "21") (name "MP10") (class "Default")
      (node (ref "JP2") (pin "10") (pinfunction "10_10") (pintype "passive"))
      (node (ref "U$1") (pin "16") (pinfunction "MP10_16") (pintype "bidirectional"))
    )
    (net (code "22") (name "MP11") (class "Default")
      (node (ref "JP2") (pin "11") (pinfunction "11_11") (pintype "passive"))
      (node (ref "U$1") (pin "19") (pinfunction "MP11_19") (pintype "bidirectional"))
    )
    (net (code "23") (name "Net-(C10-Pad1)") (class "Default")
      (node (ref "C10") (pin "1") (pinfunction "1_1") (pintype "passive"))
      (node (ref "C4") (pin "+") (pinfunction "+_+") (pintype "passive"))
      (node (ref "C9") (pin "1") (pinfunction "1_1") (pintype "passive"))
      (node (ref "T1") (pin "2") (pinfunction "C_2") (pintype "passive"))
      (node (ref "T1") (pin "4") (pinfunction "C_4") (pintype "passive"))
      (node (ref "U$1") (pin "13") (pinfunction "DVDD_13") (pintype "power_in"))
      (node (ref "U$1") (pin "24") (pinfunction "DVDD_24") (pintype "power_in"))
    )
    (net (code "24") (name "Net-(C18-Pad2)") (class "Default")
      (node (ref "C18") (pin "2") (pinfunction "2_2") (pintype "passive"))
      (node (ref "Q1") (pin "2") (pinfunction "2_2") (pintype "passive"))
      (node (ref "R6") (pin "2") (pinfunction "2_2") (pintype "passive"))
    )
    (net (code "25") (name "Net-(C20-Pad1)") (class "Default")
      (node (ref "C20") (pin "1") (pinfunction "1_1") (pintype "passive"))
      (node (ref "R7") (pin "2") (pinfunction "2_2") (pintype "passive"))
    )
    (net (code "26") (name "Net-(C21-Pad2)") (class "Default")
      (node (ref "C21") (pin "2") (pinfunction "2_2") (pintype "passive"))
      (node (ref "C47") (pin "2") (pinfunction "2_2") (pintype "passive"))
      (node (ref "R12") (pin "1") (pinfunction "1_1") (pintype "passive"))
    )
    (net (code "27") (name "Net-(C22-Pad2)") (class "Default")
      (node (ref "C22") (pin "2") (pinfunction "2_2") (pintype "passive"))
      (node (ref "C26") (pin "2") (pinfunction "2_2") (pintype "passive"))
      (node (ref "R16") (pin "1") (pinfunction "1_1") (pintype "passive"))
    )
    (net (code "28") (name "Net-(C23-Pad2)") (class "Default")
      (node (ref "C23") (pin "2") (pinfunction "2_2") (pintype "passive"))
      (node (ref "C30") (pin "2") (pinfunction "2_2") (pintype "passive"))
      (node (ref "R20") (pin "1") (pinfunction "1_1") (pintype "passive"))
    )
    (net (code "29") (name "Net-(C25-Pad1)") (class "Default")
      (node (ref "C25") (pin "1") (pinfunction "1_1") (pintype "passive"))
      (node (ref "R10") (pin "1") (pinfunction "1_1") (pintype "passive"))
      (node (ref "R9") (pin "2") (pinfunction "2_2") (pintype "passive"))
    )
    (net (code "30") (name "Net-(C28-Pad1)") (class "Default")
      (node (ref "C28") (pin "1") (pinfunction "1_1") (pintype "passive"))
      (node (ref "R12") (pin "2") (pinfunction "2_2") (pintype "passive"))
      (node (ref "R13") (pin "2") (pinfunction "2_2") (pintype "passive"))
      (node (ref "X4") (pin "1") (pinfunction "1_1") (pintype "passive"))
    )
    (net (code "31") (name "Net-(C29-Pad1)") (class "Default")
      (node (ref "C29") (pin "1") (pinfunction "1_1") (pintype "passive"))
      (node (ref "R14") (pin "2") (pinfunction "2_2") (pintype "passive"))
      (node (ref "R15") (pin "1") (pinfunction "1_1") (pintype "passive"))
    )
    (net (code "32") (name "Net-(C32-Pad1)") (class "Default")
      (node (ref "C32") (pin "1") (pinfunction "1_1") (pintype "passive"))
      (node (ref "R16") (pin "2") (pinfunction "2_2") (pintype "passive"))
      (node (ref "R17") (pin "2") (pinfunction "2_2") (pintype "passive"))
      (node (ref "X5") (pin "1") (pinfunction "1_1") (pintype "passive"))
    )
    (net (code "33") (name "Net-(C33-Pad1)") (class "Default")
      (node (ref "C33") (pin "1") (pinfunction "1_1") (pintype "passive"))
      (node (ref "R18") (pin "2") (pinfunction "2_2") (pintype "passive"))
      (node (ref "R19") (pin "1") (pinfunction "1_1") (pintype "passive"))
    )
    (net (code "34") (name "Net-(C34-Pad2)") (class "Default")
      (node (ref "C34") (pin "2") (pinfunction "2_2") (pintype "passive"))
      (node (ref "C38") (pin "2") (pinfunction "2_2") (pintype "passive"))
      (node (ref "R24") (pin "1") (pinfunction "1_1") (pintype "passive"))
    )
    (net (code "35") (name "Net-(C36-Pad1)") (class "Default")
      (node (ref "C36") (pin "1") (pinfunction "1_1") (pintype "passive"))
      (node (ref "R20") (pin "2") (pinfunction "2_2") (pintype "passive"))
      (node (ref "R21") (pin "2") (pinfunction "2_2") (pintype "passive"))
      (node (ref "X6") (pin "1") (pinfunction "1_1") (pintype "passive"))
    )
    (net (code "36") (name "Net-(C37-Pad1)") (class "Default")
      (node (ref "C37") (pin "1") (pinfunction "1_1") (pintype "passive"))
      (node (ref "R22") (pin "2") (pinfunction "2_2") (pintype "passive"))
      (node (ref "R23") (pin "1") (pinfunction "1_1") (pintype "passive"))
    )
    (net (code "37") (name "Net-(C40-Pad1)") (class "Default")
      (node (ref "C40") (pin "1") (pinfunction "1_1") (pintype "passive"))
      (node (ref "R24") (pin "2") (pinfunction "2_2") (pintype "passive"))
      (node (ref "R25") (pin "2") (pinfunction "2_2") (pintype "passive"))
      (node (ref "X7") (pin "1") (pinfunction "1_1") (pintype "passive"))
    )
    (net (code "38") (name "Net-(C41-Pad1)") (class "Default")
      (node (ref "C41") (pin "1") (pinfunction "1_1") (pintype "passive"))
      (node (ref "C43") (pin "1") (pinfunction "1_1") (pintype "passive"))
      (node (ref "C44") (pin "1") (pinfunction "1_1") (pintype "passive"))
      (node (ref "R29") (pin "2") (pinfunction "2_2") (pintype "passive"))
      (node (ref "X2") (pin "1") (pinfunction "1_1") (pintype "passive"))
    )
    (net (code "39") (name "Net-(C41-Pad2)") (class "Default")
      (node (ref "C41") (pin "2") (pinfunction "2_2") (pintype "passive"))
      (node (ref "C43") (pin "2") (pinfunction "2_2") (pintype "passive"))
      (node (ref "JP9") (pin "1") (pinfunction "1_1") (pintype "passive"))
      (node (ref "JP9") (pin "3") (pinfunction "3_3") (pintype "passive"))
      (node (ref "JP9") (pin "5") (pinfunction "5_5") (pintype "passive"))
    )
    (net (code "40") (name "Net-(C42-Pad1)") (class "Default")
      (node (ref "C42") (pin "1") (pinfunction "1_1") (pintype "passive"))
      (node (ref "C46") (pin "1") (pinfunction "1_1") (pintype "passive"))
      (node (ref "C48") (pin "1") (pinfunction "1_1") (pintype "passive"))
      (node (ref "R27") (pin "2") (pinfunction "2_2") (pintype "passive"))
      (node (ref "X1") (pin "1") (pinfunction "1_1") (pintype "passive"))
    )
    (net (code "41") (name "Net-(C46-Pad2)") (class "Default")
      (node (ref "C46") (pin "2") (pinfunction "2_2") (pintype "passive"))
      (node (ref "C48") (pin "2") (pinfunction "2_2") (pintype "passive"))
      (node (ref "JP8") (pin "1") (pinfunction "1_1") (pintype "passive"))
      (node (ref "JP8") (pin "3") (pinfunction "3_3") (pintype "passive"))
      (node (ref "JP8") (pin "5") (pinfunction "5_5") (pintype "passive"))
    )
    (net (code "42") (name "Net-(IC1-WP)") (class "Default")
      (node (ref "IC1") (pin "7") (pinfunction "WP_7") (pintype "input"))
      (node (ref "JP4") (pin "2") (pinfunction "2_2") (pintype "passive"))
    )
    (net (code "43") (name "Net-(IC3A-+IN)") (class "Default")
      (node (ref "C31") (pin "1") (pinfunction "1_1") (pintype "passive"))
      (node (ref "IC3") (pin "3") (pinfunction "+IN_3") (pintype "input"))
      (node (ref "R15") (pin "2") (pinfunction "2_2") (pintype "passive"))
    )
    (net (code "44") (name "Net-(IC3A--IN)") (class "Default")
      (node (ref "C22") (pin "1") (pinfunction "1_1") (pintype "passive"))
      (node (ref "C26") (pin "1") (pinfunction "1_1") (pintype "passive"))
      (node (ref "C29") (pin "2") (pinfunction "2_2") (pintype "passive"))
      (node (ref "IC3") (pin "1") (pinfunction "OUT_1") (pintype "output"))
      (node (ref "IC3") (pin "2") (pinfunction "-IN_2") (pintype "input"))
    )
    (net (code "45") (name "Net-(IC3B-+IN)") (class "Default")
      (node (ref "C27") (pin "1") (pinfunction "1_1") (pintype "passive"))
      (node (ref "IC3") (pin "5") (pinfunction "+IN_5") (pintype "input"))
      (node (ref "R10") (pin "2") (pinfunction "2_2") (pintype "passive"))
    )
    (net (code "46") (name "Net-(IC3B--IN)") (class "Default")
      (node (ref "C21") (pin "1") (pinfunction "1_1") (pintype "passive"))
      (node (ref "C25") (pin "2") (pinfunction "2_2") (pintype "passive"))
      (node (ref "C47") (pin "1") (pinfunction "1_1") (pintype "passive"))
      (node (ref "IC3") (pin "6") (pinfunction "-IN_6") (pintype "input"))
      (node (ref "IC3") (pin "7") (pinfunction "OUT_7") (pintype "output"))
    )
    (net (code "47") (name "Net-(IC3C-+IN)") (class "Default")
      (node (ref "C39") (pin "1") (pinfunction "1_1") (pintype "passive"))
      (node (ref "IC3") (pin "10") (pinfunction "+IN_10") (pintype "input"))
      (node (ref "R23") (pin "2") (pinfunction "2_2") (pintype "passive"))
    )
    (net (code "48") (name "Net-(IC3C--IN)") (class "Default")
      (node (ref "C34") (pin "1") (pinfunction "1_1") (pintype "passive"))
      (node (ref "C37") (pin "2") (pinfunction "2_2") (pintype "passive"))
      (node (ref "C38") (pin "1") (pinfunction "1_1") (pintype "passive"))
      (node (ref "IC3") (pin "8") (pinfunction "OUT_8") (pintype "output"))
      (node (ref "IC3") (pin "9") (pinfunction "-IN_9") (pintype "input"))
    )
    (net (code "49") (name "Net-(IC3D-+IN)") (class "Default")
      (node (ref "C35") (pin "1") (pinfunction "1_1") (pintype "passive"))
      (node (ref "IC3") (pin "12") (pinfunction "+IN_12") (pintype "input"))
      (node (ref "R19") (pin "2") (pinfunction "2_2") (pintype "passive"))
    )
    (net (code "50") (name "Net-(IC3D--IN)") (class "Default")
      (node (ref "C23") (pin "1") (pinfunction "1_1") (pintype "passive"))
      (node (ref "C30") (pin "1") (pinfunction "1_1") (pintype "passive"))
      (node (ref "C33") (pin "2") (pinfunction "2_2") (pintype "passive"))
      (node (ref "IC3") (pin "13") (pinfunction "-IN_13") (pintype "input"))
      (node (ref "IC3") (pin "14") (pinfunction "OUT_14") (pintype "output"))
    )
    (net (code "51") (name "Net-(JP8-Pad2)") (class "Default")
      (node (ref "JP8") (pin "2") (pinfunction "2_2") (pintype "passive"))
      (node (ref "R26") (pin "1") (pinfunction "1_1") (pintype "passive"))
    )
    (net (code "52") (name "Net-(JP8-Pad4)") (class "Default")
      (node (ref "JP8") (pin "4") (pinfunction "4_4") (pintype "passive"))
      (node (ref "R30") (pin "1") (pinfunction "1_1") (pintype "passive"))
    )
    (net (code "53") (name "Net-(JP8-Pad6)") (class "Default")
      (node (ref "JP8") (pin "6") (pinfunction "6_6") (pintype "passive"))
      (node (ref "R31") (pin "1") (pinfunction "1_1") (pintype "passive"))
    )
    (net (code "54") (name "Net-(JP9-Pad2)") (class "Default")
      (node (ref "JP9") (pin "2") (pinfunction "2_2") (pintype "passive"))
      (node (ref "R28") (pin "1") (pinfunction "1_1") (pintype "passive"))
    )
    (net (code "55") (name "Net-(JP9-Pad4)") (class "Default")
      (node (ref "JP9") (pin "4") (pinfunction "4_4") (pintype "passive"))
      (node (ref "R32") (pin "1") (pinfunction "1_1") (pintype "passive"))
    )
    (net (code "56") (name "Net-(JP9-Pad6)") (class "Default")
      (node (ref "JP9") (pin "6") (pinfunction "6_6") (pintype "passive"))
      (node (ref "R33") (pin "1") (pinfunction "1_1") (pintype "passive"))
    )
    (net (code "57") (name "Net-(LED1-PadA)") (class "Default")
      (node (ref "LED1") (pin "A") (pinfunction "A_A") (pintype "passive"))
      (node (ref "R8") (pin "1") (pinfunction "1_1") (pintype "passive"))
    )
    (net (code "58") (name "Net-(Q2-D)") (class "Default")
      (node (ref "JP3") (pin "16") (pinfunction "16_16") (pintype "passive"))
      (node (ref "Q2") (pin "1") (pinfunction "D_1") (pintype "passive"))
      (node (ref "R35") (pin "1") (pinfunction "1_1") (pintype "passive"))
    )
    (net (code "59") (name "Net-(Q3-D)") (class "Default")
      (node (ref "JP3") (pin "17") (pinfunction "17_17") (pintype "passive"))
      (node (ref "Q3") (pin "1") (pinfunction "D_1") (pintype "passive"))
      (node (ref "R36") (pin "1") (pinfunction "1_1") (pintype "passive"))
    )
    (net (code "60") (name "Net-(Q4-D)") (class "Default")
      (node (ref "JP3") (pin "15") (pinfunction "15_15") (pintype "passive"))
      (node (ref "Q4") (pin "1") (pinfunction "D_1") (pintype "passive"))
      (node (ref "R37") (pin "1") (pinfunction "1_1") (pintype "passive"))
    )
    (net (code "61") (name "Net-(Q5-D)") (class "Default")
      (node (ref "JP3") (pin "14") (pinfunction "14_14") (pintype "passive"))
      (node (ref "Q5") (pin "1") (pinfunction "D_1") (pintype "passive"))
      (node (ref "R38") (pin "1") (pinfunction "1_1") (pintype "passive"))
    )
    (net (code "62") (name "Net-(T1-B)") (class "Default")
      (node (ref "R1") (pin "1") (pinfunction "1_1") (pintype "passive"))
      (node (ref "T1") (pin "1") (pinfunction "B_1") (pintype "passive"))
      (node (ref "U$1") (pin "17") (pinfunction "VDRIVE_17") (pintype "bidirectional"))
    )
    (net (code "63") (name "Net-(U$1-ADC_RES)") (class "Default")
      (node (ref "R2") (pin "2") (pinfunction "2_2") (pintype "passive"))
      (node (ref "U$1") (pin "3") (pinfunction "ADC_RES_3") (pintype "bidirectional"))
    )
    (net (code "64") (name "Net-(U$1-MCLOCKI)") (class "Default")
      (node (ref "C17") (pin "2") (pinfunction "2_2") (pintype "passive"))
      (node (ref "Q1") (pin "1") (pinfunction "1_1") (pintype "passive"))
      (node (ref "U$1") (pin "32") (pinfunction "MCLOCKI_32") (pintype "bidirectional"))
    )
    (net (code "65") (name "Net-(U$1-OSCO)") (class "Default")
      (node (ref "R6") (pin "1") (pinfunction "1_1") (pintype "passive"))
      (node (ref "U$1") (pin "31") (pinfunction "OSCO_31") (pintype "bidirectional"))
    )
    (net (code "66") (name "Net-(U$1-PLL_LF)") (class "Default")
      (node (ref "C19") (pin "2") (pinfunction "2_2") (pintype "passive"))
      (node (ref "C20") (pin "2") (pinfunction "2_2") (pintype "passive"))
      (node (ref "U$1") (pin "35") (pinfunction "PLL_LF_35") (pintype "bidirectional"))
    )
    (net (code "67") (name "Net-(X3A-KL)") (class "Default")
      (node (ref "D2") (pin "A") (pinfunction "A_A") (pintype "passive"))
      (node (ref "X3") (pin "1") (pinfunction "KL_1") (pintype "passive"))
    )
    (net (code "68") (name "SCL") (class "Default")
      (node (ref "IC1") (pin "6") (pinfunction "SCL_6") (pintype "input"))
      (node (ref "JP2") (pin "15") (pinfunction "15_15") (pintype "passive"))
      (node (ref "Q4") (pin "3") (pinfunction "S_3") (pintype "passive"))
      (node (ref "R4") (pin "1") (pinfunction "1_1") (pintype "passive"))
      (node (ref "SV2") (pin "1") (pinfunction "1_1") (pintype "passive"))
      (node (ref "U$1") (pin "23") (pinfunction "SCL/CCLK_23") (pintype "bidirectional"))
    )
    (net (code "69") (name "SDA") (class "Default")
      (node (ref "IC1") (pin "5") (pinfunction "SDA_5") (pintype "bidirectional"))
      (node (ref "JP2") (pin "12") (pinfunction "12_12") (pintype "passive"))
      (node (ref "Q5") (pin "3") (pinfunction "S_3") (pintype "passive"))
      (node (ref "R5") (pin "1") (pinfunction "1_1") (pintype "passive"))
      (node (ref "SV2") (pin "3") (pinfunction "3_3") (pintype "passive"))
      (node (ref "U$1") (pin "22") (pinfunction "SDA/COUT_22") (pintype "bidirectional"))
    )
    (net (code "70") (name "SDATA_IN") (class "Default")
      (node (ref "JP2") (pin "7") (pinfunction "7_7") (pintype "passive"))
      (node (ref "U$1") (pin "11") (pinfunction "MP0_11") (pintype "bidirectional"))
    )
    (net (code "71") (name "V+") (class "Default")
      (node (ref "C49") (pin "+") (pinfunction "+_+") (pintype "passive"))
      (node (ref "C51") (pin "2") (pinfunction "2_2") (pintype "passive"))
      (node (ref "D1") (pin "C") (pinfunction "C_C") (pintype "passive"))
      (node (ref "D2") (pin "C") (pinfunction "C_C") (pintype "passive"))
      (node (ref "D3") (pin "C") (pinfunction "C_C") (pintype "passive"))
      (node (ref "U$2") (pin "OUT") (pinfunction "IN_OUT") (pintype "input"))
    )
    (net (code "72") (name "VOUT0") (class "Default")
      (node (ref "R9") (pin "1") (pinfunction "1_1") (pintype "passive"))
      (node (ref "U$1") (pin "46") (pinfunction "VOUT0_46") (pintype "bidirectional"))
    )
    (net (code "73") (name "VOUT1") (class "Default")
      (node (ref "R14") (pin "1") (pinfunction "1_1") (pintype "passive"))
      (node (ref "U$1") (pin "45") (pinfunction "VOUT1_45") (pintype "bidirectional"))
    )
    (net (code "74") (name "VOUT2") (class "Default")
      (node (ref "R18") (pin "1") (pinfunction "1_1") (pintype "passive"))
      (node (ref "U$1") (pin "44") (pinfunction "VOUT2_44") (pintype "bidirectional"))
    )
    (net (code "75") (name "VOUT3") (class "Default")
      (node (ref "R22") (pin "1") (pinfunction "1_1") (pintype "passive"))
      (node (ref "U$1") (pin "43") (pinfunction "VOUT3_43") (pintype "bidirectional"))
    )
    (net (code "76") (name "WB") (class "Default")
      (node (ref "JP2") (pin "13") (pinfunction "13_13") (pintype "passive"))
      (node (ref "U$1") (pin "20") (pinfunction "ADR1/CDATA/WB_20") (pintype "bidirectional"))
    )
    (net (code "77") (name "WP") (class "Default")
      (node (ref "JP4") (pin "1") (pinfunction "1_1") (pintype "passive"))
      (node (ref "Q2") (pin "3") (pinfunction "S_3") (pintype "passive"))
      (node (ref "R3") (pin "1") (pinfunction "1_1") (pintype "passive"))
      (node (ref "U$1") (pin "21") (pinfunction "CLATCH/WP_21") (pintype "bidirectional"))
    )
    (net (code "78") (name "unconnected-(JP3-Pad1)") (class "Default")
      (node (ref "JP3") (pin "1") (pinfunction "1_1") (pintype "passive"))
    )
    (net (code "79") (name "unconnected-(JP3-Pad2)") (class "Default")
      (node (ref "JP3") (pin "2") (pinfunction "2_2") (pintype "passive"))
    )
    (net (code "80") (name "unconnected-(JP3-Pad3)") (class "Default")
      (node (ref "JP3") (pin "3") (pinfunction "3_3") (pintype "passive"))
    )
    (net (code "81") (name "unconnected-(JP3-Pad4)") (class "Default")
      (node (ref "JP3") (pin "4") (pinfunction "4_4") (pintype "passive"))
    )
    (net (code "82") (name "unconnected-(JP3-Pad5)") (class "Default")
      (node (ref "JP3") (pin "5") (pinfunction "5_5") (pintype "passive"))
    )
    (net (code "83") (name "unconnected-(JP3-Pad7)") (class "Default")
      (node (ref "JP3") (pin "7") (pinfunction "7_7") (pintype "passive"))
    )
    (net (code "84") (name "unconnected-(JP3-Pad8)") (class "Default")
      (node (ref "JP3") (pin "8") (pinfunction "8_8") (pintype "passive"))
    )
    (net (code "85") (name "unconnected-(JP3-Pad9)") (class "Default")
      (node (ref "JP3") (pin "9") (pinfunction "9_9") (pintype "passive"))
    )
    (net (code "86") (name "unconnected-(JP3-Pad10)") (class "Default")
      (node (ref "JP3") (pin "10") (pinfunction "10_10") (pintype "passive"))
    )
    (net (code "87") (name "unconnected-(JP3-Pad11)") (class "Default")
      (node (ref "JP3") (pin "11") (pinfunction "11_11") (pintype "passive"))
    )
    (net (code "88") (name "unconnected-(JP3-Pad12)") (class "Default")
      (node (ref "JP3") (pin "12") (pinfunction "12_12") (pintype "passive"))
    )
    (net (code "89") (name "unconnected-(JP3-Pad13)") (class "Default")
      (node (ref "JP3") (pin "13") (pinfunction "13_13") (pintype "passive"))
    )
    (net (code "90") (name "unconnected-(JP5-Pad1)") (class "Default")
      (node (ref "JP5") (pin "1") (pinfunction "1_1") (pintype "passive"))
    )
    (net (code "91") (name "unconnected-(JP5-Pad2)") (class "Default")
      (node (ref "JP5") (pin "2") (pinfunction "2_2") (pintype "passive"))
    )
    (net (code "92") (name "unconnected-(JP5-Pad3)") (class "Default")
      (node (ref "JP5") (pin "3") (pinfunction "3_3") (pintype "passive"))
    )
    (net (code "93") (name "unconnected-(JP5-Pad5)") (class "Default")
      (node (ref "JP5") (pin "5") (pinfunction "5_5") (pintype "passive"))
    )
    (net (code "94") (name "unconnected-(JP5-Pad7)") (class "Default")
      (node (ref "JP5") (pin "7") (pinfunction "7_7") (pintype "passive"))
    )
    (net (code "95") (name "unconnected-(JP5-Pad8)") (class "Default")
      (node (ref "JP5") (pin "8") (pinfunction "8_8") (pintype "passive"))
    )
    (net (code "96") (name "unconnected-(JP5-Pad9)") (class "Default")
      (node (ref "JP5") (pin "9") (pinfunction "9_9") (pintype "passive"))
    )
    (net (code "97") (name "unconnected-(JP5-Pad10)") (class "Default")
      (node (ref "JP5") (pin "10") (pinfunction "10_10") (pintype "passive"))
    )
    (net (code "98") (name "unconnected-(JP5-Pad11)") (class "Default")
      (node (ref "JP5") (pin "11") (pinfunction "11_11") (pintype "passive"))
    )
    (net (code "99") (name "unconnected-(JP5-Pad12)") (class "Default")
      (node (ref "JP5") (pin "12") (pinfunction "12_12") (pintype "passive"))
    )
    (net (code "100") (name "unconnected-(JP5-Pad13)") (class "Default")
      (node (ref "JP5") (pin "13") (pinfunction "13_13") (pintype "passive"))
    )
    (net (code "101") (name "unconnected-(JP5-Pad14)") (class "Default")
      (node (ref "JP5") (pin "14") (pinfunction "14_14") (pintype "passive"))
    )
    (net (code "102") (name "unconnected-(JP5-Pad15)") (class "Default")
      (node (ref "JP5") (pin "15") (pinfunction "15_15") (pintype "passive"))
    )
    (net (code "103") (name "unconnected-(JP5-Pad16)") (class "Default")
      (node (ref "JP5") (pin "16") (pinfunction "16_16") (pintype "passive"))
    )
    (net (code "104") (name "unconnected-(JP5-Pad17)") (class "Default")
      (node (ref "JP5") (pin "17") (pinfunction "17_17") (pintype "passive"))
    )
    (net (code "105") (name "unconnected-(SV2-Pad2)") (class "Default")
      (node (ref "SV2") (pin "2") (pinfunction "2_2") (pintype "passive"))
    )
    (net (code "106") (name "unconnected-(SV2-Pad5)") (class "Default")
      (node (ref "SV2") (pin "5") (pinfunction "5_5") (pintype "passive"))
    )
    (net (code "107") (name "unconnected-(SV2-Pad7)") (class "Default")
      (node (ref "SV2") (pin "7") (pinfunction "7_7") (pintype "passive"))
    )
    (net (code "108") (name "unconnected-(SV2-Pad8)") (class "Default")
      (node (ref "SV2") (pin "8") (pinfunction "8_8") (pintype "passive"))
    )
    (net (code "109") (name "unconnected-(SV2-Pad9)") (class "Default")
      (node (ref "SV2") (pin "9") (pinfunction "9_9") (pintype "passive"))
    )
  )
)
